# 01power.net
KiCad netlist of a schematic drawn in Altium Designer
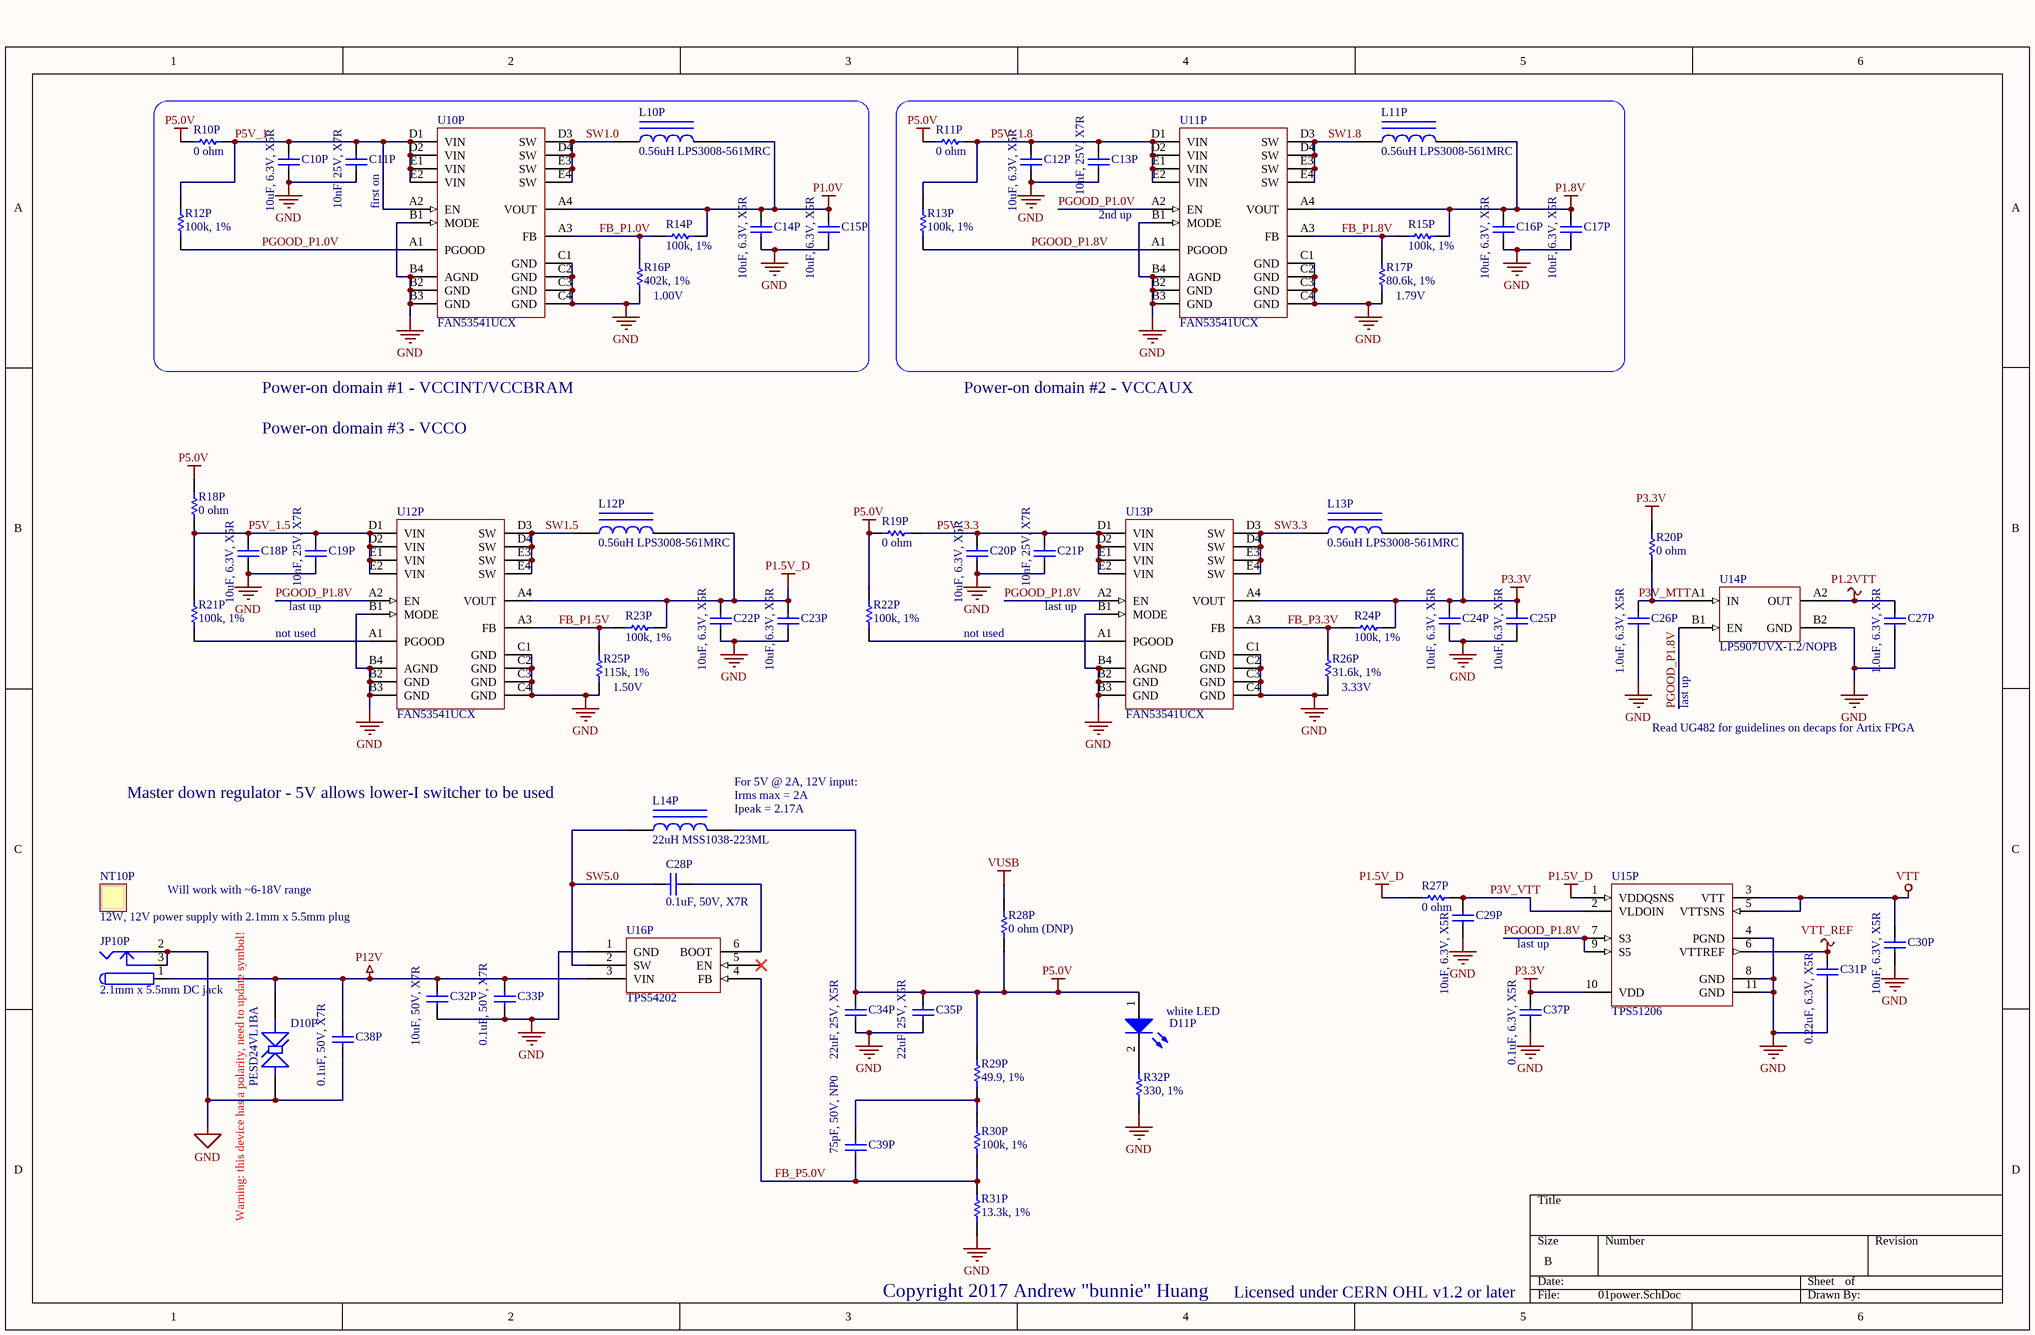
[diagram p0: 01power.SchDoc]

(export (version "E")
  (design (tool "Eeschema 10.0.6"))
  (components
    (comp (ref "C10P")
      (value "10uF, 6.3V, X5R")
      (footprint "CAPC1608N")
      (description "Capacitor (Semiconductor SIM Model)")
      (fields (field (name "MPN") "CL10A106MQ8NNNC"))
      (libsource (lib "Miscellaneous Devices") (part "Cap Semi"))
    )
    (comp (ref "C11P")
      (value "10nF, 25V, X7R")
      (footprint "CAPC1005N")
      (description "Capacitor (Semiconductor SIM Model)")
      (fields (field (name "MPN") "CL05B103KA5NNNC"))
      (libsource (lib "Miscellaneous Devices") (part "Cap Semi"))
    )
    (comp (ref "C12P")
      (value "10uF, 6.3V, X5R")
      (footprint "CAPC1608N")
      (description "Capacitor (Semiconductor SIM Model)")
      (fields (field (name "MPN") "CL10A106MQ8NNNC"))
      (libsource (lib "Miscellaneous Devices") (part "Cap Semi"))
    )
    (comp (ref "C13P")
      (value "10nF, 25V, X7R")
      (footprint "CAPC1005N")
      (description "Capacitor (Semiconductor SIM Model)")
      (fields (field (name "MPN") "CL05B103KA5NNNC"))
      (libsource (lib "Miscellaneous Devices") (part "Cap Semi"))
    )
    (comp (ref "C14P")
      (value "10uF, 6.3V, X5R")
      (footprint "CAPC1608N")
      (description "Capacitor (Semiconductor SIM Model)")
      (fields (field (name "MPN") "CL10A106MQ8NNNC"))
      (libsource (lib "Miscellaneous Devices") (part "Cap Semi"))
    )
    (comp (ref "C15P")
      (value "10uF, 6.3V, X5R")
      (footprint "CAPC1608N")
      (description "Capacitor (Semiconductor SIM Model)")
      (fields (field (name "MPN") "CL10A106MQ8NNNC"))
      (libsource (lib "Miscellaneous Devices") (part "Cap Semi"))
    )
    (comp (ref "C16P")
      (value "10uF, 6.3V, X5R")
      (footprint "CAPC1608N")
      (description "Capacitor (Semiconductor SIM Model)")
      (fields (field (name "MPN") "CL10A106MQ8NNNC"))
      (libsource (lib "Miscellaneous Devices") (part "Cap Semi"))
    )
    (comp (ref "C17P")
      (value "10uF, 6.3V, X5R")
      (footprint "CAPC1608N")
      (description "Capacitor (Semiconductor SIM Model)")
      (fields (field (name "MPN") "CL10A106MQ8NNNC"))
      (libsource (lib "Miscellaneous Devices") (part "Cap Semi"))
    )
    (comp (ref "C18P")
      (value "10uF, 6.3V, X5R")
      (footprint "CAPC1608N")
      (description "Capacitor (Semiconductor SIM Model)")
      (fields (field (name "MPN") "CL10A106MQ8NNNC"))
      (libsource (lib "Miscellaneous Devices") (part "Cap Semi"))
    )
    (comp (ref "C19P")
      (value "10nF, 25V, X7R")
      (footprint "CAPC1005N")
      (description "Capacitor (Semiconductor SIM Model)")
      (fields (field (name "MPN") "CL05B103KA5NNNC"))
      (libsource (lib "Miscellaneous Devices") (part "Cap Semi"))
    )
    (comp (ref "C20P")
      (value "10uF, 6.3V, X5R")
      (footprint "CAPC1608N")
      (description "Capacitor (Semiconductor SIM Model)")
      (fields (field (name "MPN") "CL10A106MQ8NNNC"))
      (libsource (lib "Miscellaneous Devices") (part "Cap Semi"))
    )
    (comp (ref "C21P")
      (value "10nF, 25V, X7R")
      (footprint "CAPC1005N")
      (description "Capacitor (Semiconductor SIM Model)")
      (fields (field (name "MPN") "CL05B103KA5NNNC"))
      (libsource (lib "Miscellaneous Devices") (part "Cap Semi"))
    )
    (comp (ref "C22P")
      (value "10uF, 6.3V, X5R")
      (footprint "CAPC1608N")
      (description "Capacitor (Semiconductor SIM Model)")
      (fields (field (name "MPN") "CL10A106MQ8NNNC"))
      (libsource (lib "Miscellaneous Devices") (part "Cap Semi"))
    )
    (comp (ref "C23P")
      (value "10uF, 6.3V, X5R")
      (footprint "CAPC1608N")
      (description "Capacitor (Semiconductor SIM Model)")
      (fields (field (name "MPN") "CL10A106MQ8NNNC"))
      (libsource (lib "Miscellaneous Devices") (part "Cap Semi"))
    )
    (comp (ref "C24P")
      (value "10uF, 6.3V, X5R")
      (footprint "CAPC1608N")
      (description "Capacitor (Semiconductor SIM Model)")
      (fields (field (name "MPN") "CL10A106MQ8NNNC"))
      (libsource (lib "Miscellaneous Devices") (part "Cap Semi"))
    )
    (comp (ref "C25P")
      (value "10uF, 6.3V, X5R")
      (footprint "CAPC1608N")
      (description "Capacitor (Semiconductor SIM Model)")
      (fields (field (name "MPN") "CL10A106MQ8NNNC"))
      (libsource (lib "Miscellaneous Devices") (part "Cap Semi"))
    )
    (comp (ref "C26P")
      (value "1.0uF, 6.3V, X5R")
      (footprint "CAPC0603X03L")
      (description "Capacitor (Semiconductor SIM Model)")
      (fields (field (name "MPN") "CL03A105KQ3CSNC"))
      (libsource (lib "Miscellaneous Devices") (part "Cap Semi"))
    )
    (comp (ref "C27P")
      (value "1.0uF, 6.3V, X5R")
      (footprint "CAPC0603X03L")
      (description "Capacitor (Semiconductor SIM Model)")
      (fields (field (name "MPN") "CL03A105KQ3CSNC"))
      (libsource (lib "Miscellaneous Devices") (part "Cap Semi"))
    )
    (comp (ref "C28P")
      (value "0.1uF, 50V, X7R")
      (footprint "CAPC2012N")
      (description "Capacitor (Semiconductor SIM Model)")
      (fields (field (name "MPN") "CL21B104KBCNNWC"))
      (libsource (lib "Miscellaneous Devices") (part "Cap Semi"))
    )
    (comp (ref "C29P")
      (value "10uF, 6.3V, X5R")
      (footprint "CAPC1608N")
      (description "Capacitor (Semiconductor SIM Model)")
      (fields (field (name "MPN") "CL10A106MQ8NNNC"))
      (libsource (lib "Miscellaneous Devices") (part "Cap Semi"))
    )
    (comp (ref "C30P")
      (value "10uF, 6.3V, X5R")
      (footprint "CAPC1608N")
      (description "Capacitor (Semiconductor SIM Model)")
      (fields (field (name "MPN") "CL10A106MQ8NNNC"))
      (libsource (lib "Miscellaneous Devices") (part "Cap Semi"))
    )
    (comp (ref "C31P")
      (value "0.22uF, 6.3V, X5R")
      (footprint "CAPC0603X03L")
      (description "Capacitor (Semiconductor SIM Model)")
      (fields (field (name "MPN") "CL03A224MQ3NNNC"))
      (libsource (lib "Miscellaneous Devices") (part "Cap Semi"))
    )
    (comp (ref "C32P")
      (value "10uF, 50V, X7R")
      (footprint "CAPC3216N")
      (description "Capacitor (Semiconductor SIM Model)")
      (fields (field (name "MPN") "CL31A106KBHNNNE"))
      (libsource (lib "Miscellaneous Devices") (part "Cap Semi"))
    )
    (comp (ref "C33P")
      (value "0.1uF, 50V, X7R")
      (footprint "CAPC2012N")
      (description "Capacitor (Semiconductor SIM Model)")
      (fields (field (name "MPN") "CL21B104KBCNNWC"))
      (libsource (lib "Miscellaneous Devices") (part "Cap Semi"))
    )
    (comp (ref "C34P")
      (value "22uF, 25V, X5R")
      (footprint "CAPC3216N")
      (description "Capacitor (Semiconductor SIM Model)")
      (fields (field (name "MPN") "CL31A226KAHNNNE"))
      (libsource (lib "Miscellaneous Devices") (part "Cap Semi"))
    )
    (comp (ref "C35P")
      (value "22uF, 25V, X5R")
      (footprint "CAPC3216N")
      (description "Capacitor (Semiconductor SIM Model)")
      (fields (field (name "MPN") "CL31A226KAHNNNE"))
      (libsource (lib "Miscellaneous Devices") (part "Cap Semi"))
    )
    (comp (ref "C37P")
      (value "0.1uF, 6.3V, X5R")
      (footprint "CAPC0603X03L")
      (description "Capacitor (Semiconductor SIM Model)")
      (fields (field (name "MPN") "CL03A104KQ3NNNC"))
      (libsource (lib "Miscellaneous Devices") (part "Cap Semi"))
    )
    (comp (ref "C38P")
      (value "0.1uF, 50V, X7R")
      (footprint "CAPC2012N")
      (description "Capacitor (Semiconductor SIM Model)")
      (fields (field (name "MPN") "CL21B104KBCNNWC"))
      (libsource (lib "Miscellaneous Devices") (part "Cap Semi"))
    )
    (comp (ref "C39P")
      (value "75pF, 50V, NP0")
      (footprint "CAPC1005N")
      (description "Capacitor (Semiconductor SIM Model)")
      (fields (field (name "MPN") "CL05C750JB5NNNC"))
      (libsource (lib "Miscellaneous Devices") (part "Cap Semi"))
    )
    (comp (ref "D10P")
      (value "PESD24VL1BA")
      (footprint "SOD-323")
      (description "Bidirectional zener diode, Vz 17.1V nom")
      (fields (field (name "MPN") "PESD24VL1BA,115"))
      (libsource (lib "commonsch") (part "BIDIR_ESD"))
    )
    (comp (ref "D11P")
      (value "white LED")
      (footprint "CD2012-0805")
      (description "Typical RED, GREEN, YELLOW, AMBER GaAs LED")
      (fields (field (name "MPN") "CB-2012QWC-P8"))
      (libsource (lib "Miscellaneous Devices") (part "LED2"))
    )
    (comp (ref "JP10P")
      (value "2.1mm x 5.5mm DC jack")
      (footprint "CUI_PJ_002AH_SMT")
      (description "Low Voltage Power Supply Connector")
      (fields (field (name "MPN") "PJ-002AH-SMT-TR") (field (name "PUBLISHER") "Altium Limited"))
      (libsource (lib "Miscellaneous Connectors") (part "PWR2.5"))
    )
    (comp (ref "L10P")
      (value "0.56uH LPS3008-561MRC")
      (footprint "COILCRAFT_LPS3008")
      (description "Magnetic-Core Inductor")
      (fields (field (name "MPN") "LPS3008-561MRC"))
      (libsource (lib "Miscellaneous Devices") (part "Inductor Iron"))
    )
    (comp (ref "L11P")
      (value "0.56uH LPS3008-561MRC")
      (footprint "COILCRAFT_LPS3008")
      (description "Magnetic-Core Inductor")
      (fields (field (name "MPN") "LPS3008-561MRC"))
      (libsource (lib "Miscellaneous Devices") (part "Inductor Iron"))
    )
    (comp (ref "L12P")
      (value "0.56uH LPS3008-561MRC")
      (footprint "COILCRAFT_LPS3008")
      (description "Magnetic-Core Inductor")
      (fields (field (name "MPN") "LPS3008-561MRC"))
      (libsource (lib "Miscellaneous Devices") (part "Inductor Iron"))
    )
    (comp (ref "L13P")
      (value "0.56uH LPS3008-561MRC")
      (footprint "COILCRAFT_LPS3008")
      (description "Magnetic-Core Inductor")
      (fields (field (name "MPN") "LPS3008-561MRC"))
      (libsource (lib "Miscellaneous Devices") (part "Inductor Iron"))
    )
    (comp (ref "L14P")
      (value "22uH MSS1038-223ML")
      (footprint "COILCRAFT_MSS1038")
      (description "Magnetic-Core Inductor")
      (fields (field (name "MPN") "MSS1038-223MLB"))
      (libsource (lib "Miscellaneous Devices") (part "Inductor Iron"))
    )
    (comp (ref "NT10P")
      (value "12W, 12V power supply with 2.1mm x 5.5mm plug")
      (description "Placeholder for non-board BOM items")
      (fields (field (name "MPN") "ANY"))
      (libsource (lib "commonsch") (part "NOTE"))
    )
    (comp (ref "R10P")
      (value "0 ohm")
      (footprint "RESC1608N")
      (description "Resistor")
      (fields (field (name "MPN") "ANY"))
      (libsource (lib "Miscellaneous Devices") (part "Res1"))
    )
    (comp (ref "R11P")
      (value "0 ohm")
      (footprint "RESC1608N")
      (description "Resistor")
      (fields (field (name "MPN") "ANY"))
      (libsource (lib "Miscellaneous Devices") (part "Res1"))
    )
    (comp (ref "R12P")
      (value "100k, 1%")
      (footprint "RESC1005N")
      (description "Resistor")
      (fields (field (name "MPN") "ANY"))
      (libsource (lib "Miscellaneous Devices") (part "Res1"))
    )
    (comp (ref "R13P")
      (value "100k, 1%")
      (footprint "RESC1005N")
      (description "Resistor")
      (fields (field (name "MPN") "ANY"))
      (libsource (lib "Miscellaneous Devices") (part "Res1"))
    )
    (comp (ref "R14P")
      (value "100k, 1%")
      (footprint "RESC1005N")
      (description "Resistor")
      (fields (field (name "MPN") "ANY"))
      (libsource (lib "Miscellaneous Devices") (part "Res1"))
    )
    (comp (ref "R15P")
      (value "100k, 1%")
      (footprint "RESC1005N")
      (description "Resistor")
      (fields (field (name "MPN") "ANY"))
      (libsource (lib "Miscellaneous Devices") (part "Res1"))
    )
    (comp (ref "R16P")
      (value "402k, 1%")
      (footprint "RESC1005N")
      (description "Resistor")
      (fields (field (name "MPN") "ANY"))
      (libsource (lib "Miscellaneous Devices") (part "Res1"))
    )
    (comp (ref "R17P")
      (value "80.6k, 1%")
      (footprint "RESC1005N")
      (description "Resistor")
      (fields (field (name "MPN") "ANY"))
      (libsource (lib "Miscellaneous Devices") (part "Res1"))
    )
    (comp (ref "R18P")
      (value "0 ohm")
      (footprint "RESC1608N")
      (description "Resistor")
      (fields (field (name "MPN") "ANY"))
      (libsource (lib "Miscellaneous Devices") (part "Res1"))
    )
    (comp (ref "R19P")
      (value "0 ohm")
      (footprint "RESC1608N")
      (description "Resistor")
      (fields (field (name "MPN") "ANY"))
      (libsource (lib "Miscellaneous Devices") (part "Res1"))
    )
    (comp (ref "R20P")
      (value "0 ohm")
      (footprint "RESC1608N")
      (description "Resistor")
      (fields (field (name "MPN") "ANY"))
      (libsource (lib "Miscellaneous Devices") (part "Res1"))
    )
    (comp (ref "R21P")
      (value "100k, 1%")
      (footprint "RESC1005N")
      (description "Resistor")
      (fields (field (name "MPN") "ANY"))
      (libsource (lib "Miscellaneous Devices") (part "Res1"))
    )
    (comp (ref "R22P")
      (value "100k, 1%")
      (footprint "RESC1005N")
      (description "Resistor")
      (fields (field (name "MPN") "ANY"))
      (libsource (lib "Miscellaneous Devices") (part "Res1"))
    )
    (comp (ref "R23P")
      (value "100k, 1%")
      (footprint "RESC1005N")
      (description "Resistor")
      (fields (field (name "MPN") "ANY"))
      (libsource (lib "Miscellaneous Devices") (part "Res1"))
    )
    (comp (ref "R24P")
      (value "100k, 1%")
      (footprint "RESC1005N")
      (description "Resistor")
      (fields (field (name "MPN") "ANY"))
      (libsource (lib "Miscellaneous Devices") (part "Res1"))
    )
    (comp (ref "R25P")
      (value "115k, 1%")
      (footprint "RESC1005N")
      (description "Resistor")
      (fields (field (name "MPN") "ANY"))
      (libsource (lib "Miscellaneous Devices") (part "Res1"))
    )
    (comp (ref "R26P")
      (value "31.6k, 1%")
      (footprint "RESC1005N")
      (description "Resistor")
      (fields (field (name "MPN") "ANY"))
      (libsource (lib "Miscellaneous Devices") (part "Res1"))
    )
    (comp (ref "R27P")
      (value "0 ohm")
      (footprint "RESC1608N")
      (description "Resistor")
      (fields (field (name "MPN") "ANY"))
      (libsource (lib "Miscellaneous Devices") (part "Res1"))
    )
    (comp (ref "R28P")
      (value "0 ohm (DNP)")
      (footprint "RESC1608N")
      (description "Resistor")
      (fields (field (name "MPN") "DNP"))
      (libsource (lib "Miscellaneous Devices") (part "Res1"))
    )
    (comp (ref "R29P")
      (value "49.9, 1%")
      (footprint "RESC1005N")
      (description "Resistor")
      (fields (field (name "MPN") "ANY"))
      (libsource (lib "Miscellaneous Devices") (part "Res1"))
    )
    (comp (ref "R30P")
      (value "100k, 1%")
      (footprint "RESC1005N")
      (description "Resistor")
      (fields (field (name "MPN") "ANY"))
      (libsource (lib "Miscellaneous Devices") (part "Res1"))
    )
    (comp (ref "R31P")
      (value "13.3k, 1%")
      (footprint "RESC1005N")
      (description "Resistor")
      (fields (field (name "MPN") "ANY"))
      (libsource (lib "Miscellaneous Devices") (part "Res1"))
    )
    (comp (ref "R32P")
      (value "330, 1%")
      (footprint "RESC1005N")
      (description "Resistor")
      (fields (field (name "MPN") "RS02U331FT"))
      (libsource (lib "Miscellaneous Devices") (part "Res1"))
    )
    (comp (ref "U10P")
      (value "FAN53541UCX")
      (footprint "BGA20C40P4X5_156X196X62")
      (description "2.4MHz, 5A TinyBuck Synchronous Buck Regulator")
      (libsource (lib "commonsch-new") (part "FAN53541UCX"))
    )
    (comp (ref "U11P")
      (value "FAN53541UCX")
      (footprint "BGA20C40P4X5_156X196X62")
      (description "2.4MHz, 5A TinyBuck Synchronous Buck Regulator")
      (libsource (lib "commonsch-new") (part "FAN53541UCX"))
    )
    (comp (ref "U12P")
      (value "FAN53541UCX")
      (footprint "BGA20C40P4X5_156X196X62")
      (description "2.4MHz, 5A TinyBuck Synchronous Buck Regulator")
      (libsource (lib "commonsch-new") (part "FAN53541UCX"))
    )
    (comp (ref "U13P")
      (value "FAN53541UCX")
      (footprint "BGA20C40P4X5_156X196X62")
      (description "2.4MHz, 5A TinyBuck Synchronous Buck Regulator")
      (libsource (lib "commonsch-new") (part "FAN53541UCX"))
    )
    (comp (ref "U14P")
      (value "LP5907UVX-1.2/NOPB")
      (footprint "TI_YKE004")
      (description "Ultra low-noise 250mA LDO for RF and analog in DSBGA")
      (libsource (lib "commonsch-new") (part "LP5907UVX"))
    )
    (comp (ref "U15P")
      (value "TPS51206")
      (footprint "TI-DSQ-R-PWSON-N10")
      (description "2A-peak sink/source DDR termination regulator")
      (fields (field (name "MPN") "TPS51206DSQ(T/R)"))
      (libsource (lib "temp-to-merge") (part "TPS51206"))
    )
    (comp (ref "U16P")
      (value "TPS54202")
      (footprint "SOT26A-6N")
      (description "4.5 to 28V input, 2A output, step down sync buck")
      (fields (field (name "MPN") "TPS54202DDCT"))
      (libsource (lib "commonsch-new") (part "TPS54202"))
    )
  )
  (nets
    (net (code "1") (name "/FB_P1.0V") (class "Default")
      (node (ref "R14P") (pin "1") (pinfunction "1_1") (pintype "passive"))
      (node (ref "R16P") (pin "1") (pinfunction "1_1") (pintype "passive"))
      (node (ref "U10P") (pin "A3") (pinfunction "FB_A3") (pintype "passive"))
    )
    (net (code "2") (name "/FB_P1.5V") (class "Default")
      (node (ref "R23P") (pin "1") (pinfunction "1_1") (pintype "passive"))
      (node (ref "R25P") (pin "1") (pinfunction "1_1") (pintype "passive"))
      (node (ref "U12P") (pin "A3") (pinfunction "FB_A3") (pintype "passive"))
    )
    (net (code "3") (name "/FB_P1.8V") (class "Default")
      (node (ref "R15P") (pin "1") (pinfunction "1_1") (pintype "passive"))
      (node (ref "R17P") (pin "1") (pinfunction "1_1") (pintype "passive"))
      (node (ref "U11P") (pin "A3") (pinfunction "FB_A3") (pintype "passive"))
    )
    (net (code "4") (name "/FB_P3.3V") (class "Default")
      (node (ref "R24P") (pin "1") (pinfunction "1_1") (pintype "passive"))
      (node (ref "R26P") (pin "1") (pinfunction "1_1") (pintype "passive"))
      (node (ref "U13P") (pin "A3") (pinfunction "FB_A3") (pintype "passive"))
    )
    (net (code "5") (name "/FB_P5.0V") (class "Default")
      (node (ref "C39P") (pin "2") (pinfunction "2_2") (pintype "passive"))
      (node (ref "R30P") (pin "1") (pinfunction "1_1") (pintype "passive"))
      (node (ref "R31P") (pin "2") (pinfunction "2_2") (pintype "passive"))
      (node (ref "U16P") (pin "4") (pinfunction "FB_4") (pintype "input"))
    )
    (net (code "6") (name "/P3V_MTT") (class "Default")
      (node (ref "C26P") (pin "1") (pinfunction "1_1") (pintype "passive"))
      (node (ref "R20P") (pin "1") (pinfunction "1_1") (pintype "passive"))
      (node (ref "U14P") (pin "A1") (pinfunction "IN_A1") (pintype "input"))
    )
    (net (code "7") (name "/P3V_VTT") (class "Default")
      (node (ref "C29P") (pin "1") (pinfunction "1_1") (pintype "passive"))
      (node (ref "R27P") (pin "1") (pinfunction "1_1") (pintype "passive"))
      (node (ref "U15P") (pin "2") (pinfunction "VLDOIN_2") (pintype "power_in"))
    )
    (net (code "8") (name "/P5V_1") (class "Default")
      (node (ref "C10P") (pin "1") (pinfunction "1_1") (pintype "passive"))
      (node (ref "C11P") (pin "1") (pinfunction "1_1") (pintype "passive"))
      (node (ref "R10P") (pin "2") (pinfunction "2_2") (pintype "passive"))
      (node (ref "R12P") (pin "2") (pinfunction "2_2") (pintype "passive"))
      (node (ref "U10P") (pin "A2") (pinfunction "EN_A2") (pintype "input"))
      (node (ref "U10P") (pin "D1") (pinfunction "VIN_D1") (pintype "power_in"))
      (node (ref "U10P") (pin "D2") (pinfunction "VIN_D2") (pintype "power_in"))
      (node (ref "U10P") (pin "E1") (pinfunction "VIN_E1") (pintype "power_in"))
      (node (ref "U10P") (pin "E2") (pinfunction "VIN_E2") (pintype "power_in"))
    )
    (net (code "9") (name "/P5V_1.5") (class "Default")
      (node (ref "C18P") (pin "1") (pinfunction "1_1") (pintype "passive"))
      (node (ref "C19P") (pin "1") (pinfunction "1_1") (pintype "passive"))
      (node (ref "R18P") (pin "2") (pinfunction "2_2") (pintype "passive"))
      (node (ref "R21P") (pin "1") (pinfunction "1_1") (pintype "passive"))
      (node (ref "U12P") (pin "D1") (pinfunction "VIN_D1") (pintype "power_in"))
      (node (ref "U12P") (pin "D2") (pinfunction "VIN_D2") (pintype "power_in"))
      (node (ref "U12P") (pin "E1") (pinfunction "VIN_E1") (pintype "power_in"))
      (node (ref "U12P") (pin "E2") (pinfunction "VIN_E2") (pintype "power_in"))
    )
    (net (code "10") (name "/P5V_1.8") (class "Default")
      (node (ref "C12P") (pin "1") (pinfunction "1_1") (pintype "passive"))
      (node (ref "C13P") (pin "1") (pinfunction "1_1") (pintype "passive"))
      (node (ref "R11P") (pin "2") (pinfunction "2_2") (pintype "passive"))
      (node (ref "R13P") (pin "2") (pinfunction "2_2") (pintype "passive"))
      (node (ref "U11P") (pin "D1") (pinfunction "VIN_D1") (pintype "power_in"))
      (node (ref "U11P") (pin "D2") (pinfunction "VIN_D2") (pintype "power_in"))
      (node (ref "U11P") (pin "E1") (pinfunction "VIN_E1") (pintype "power_in"))
      (node (ref "U11P") (pin "E2") (pinfunction "VIN_E2") (pintype "power_in"))
    )
    (net (code "11") (name "/P5V_3.3") (class "Default")
      (node (ref "C20P") (pin "1") (pinfunction "1_1") (pintype "passive"))
      (node (ref "C21P") (pin "1") (pinfunction "1_1") (pintype "passive"))
      (node (ref "R19P") (pin "2") (pinfunction "2_2") (pintype "passive"))
      (node (ref "U13P") (pin "D1") (pinfunction "VIN_D1") (pintype "power_in"))
      (node (ref "U13P") (pin "D2") (pinfunction "VIN_D2") (pintype "power_in"))
      (node (ref "U13P") (pin "E1") (pinfunction "VIN_E1") (pintype "power_in"))
      (node (ref "U13P") (pin "E2") (pinfunction "VIN_E2") (pintype "power_in"))
    )
    (net (code "12") (name "/PGOOD_P1.0V") (class "Default")
      (node (ref "R12P") (pin "1") (pinfunction "1_1") (pintype "passive"))
      (node (ref "U10P") (pin "A1") (pinfunction "PGOOD_A1") (pintype "open_collector"))
      (node (ref "U11P") (pin "A2") (pinfunction "EN_A2") (pintype "input"))
    )
    (net (code "13") (name "/PGOOD_P1.8V") (class "Default")
      (node (ref "R13P") (pin "1") (pinfunction "1_1") (pintype "passive"))
      (node (ref "U11P") (pin "A1") (pinfunction "PGOOD_A1") (pintype "open_collector"))
      (node (ref "U12P") (pin "A2") (pinfunction "EN_A2") (pintype "input"))
      (node (ref "U13P") (pin "A2") (pinfunction "EN_A2") (pintype "input"))
      (node (ref "U14P") (pin "B1") (pinfunction "EN_B1") (pintype "input"))
      (node (ref "U15P") (pin "7") (pinfunction "S3_7") (pintype "input"))
      (node (ref "U15P") (pin "9") (pinfunction "S5_9") (pintype "input"))
    )
    (net (code "14") (name "/SW1.0") (class "Default")
      (node (ref "L10P") (pin "1") (pinfunction "1_1") (pintype "passive"))
      (node (ref "U10P") (pin "D3") (pinfunction "SW_D3") (pintype "power_in"))
      (node (ref "U10P") (pin "D4") (pinfunction "SW_D4") (pintype "power_in"))
      (node (ref "U10P") (pin "E3") (pinfunction "SW_E3") (pintype "power_in"))
      (node (ref "U10P") (pin "E4") (pinfunction "SW_E4") (pintype "power_in"))
    )
    (net (code "15") (name "/SW1.5") (class "Default")
      (node (ref "L12P") (pin "1") (pinfunction "1_1") (pintype "passive"))
      (node (ref "U12P") (pin "D3") (pinfunction "SW_D3") (pintype "power_in"))
      (node (ref "U12P") (pin "D4") (pinfunction "SW_D4") (pintype "power_in"))
      (node (ref "U12P") (pin "E3") (pinfunction "SW_E3") (pintype "power_in"))
      (node (ref "U12P") (pin "E4") (pinfunction "SW_E4") (pintype "power_in"))
    )
    (net (code "16") (name "/SW1.8") (class "Default")
      (node (ref "L11P") (pin "1") (pinfunction "1_1") (pintype "passive"))
      (node (ref "U11P") (pin "D3") (pinfunction "SW_D3") (pintype "power_in"))
      (node (ref "U11P") (pin "D4") (pinfunction "SW_D4") (pintype "power_in"))
      (node (ref "U11P") (pin "E3") (pinfunction "SW_E3") (pintype "power_in"))
      (node (ref "U11P") (pin "E4") (pinfunction "SW_E4") (pintype "power_in"))
    )
    (net (code "17") (name "/SW3.3") (class "Default")
      (node (ref "L13P") (pin "1") (pinfunction "1_1") (pintype "passive"))
      (node (ref "U13P") (pin "D3") (pinfunction "SW_D3") (pintype "power_in"))
      (node (ref "U13P") (pin "D4") (pinfunction "SW_D4") (pintype "power_in"))
      (node (ref "U13P") (pin "E3") (pinfunction "SW_E3") (pintype "power_in"))
      (node (ref "U13P") (pin "E4") (pinfunction "SW_E4") (pintype "power_in"))
    )
    (net (code "18") (name "/SW5.0") (class "Default")
      (node (ref "C28P") (pin "1") (pinfunction "1_1") (pintype "passive"))
      (node (ref "L14P") (pin "1") (pinfunction "1_1") (pintype "passive"))
      (node (ref "U16P") (pin "2") (pinfunction "SW_2") (pintype "passive"))
    )
    (net (code "19") (name "GND") (class "Default")
      (node (ref "C10P") (pin "2") (pinfunction "2_2") (pintype "passive"))
      (node (ref "C11P") (pin "2") (pinfunction "2_2") (pintype "passive"))
      (node (ref "C12P") (pin "2") (pinfunction "2_2") (pintype "passive"))
      (node (ref "C13P") (pin "2") (pinfunction "2_2") (pintype "passive"))
      (node (ref "C14P") (pin "2") (pinfunction "2_2") (pintype "passive"))
      (node (ref "C15P") (pin "2") (pinfunction "2_2") (pintype "passive"))
      (node (ref "C16P") (pin "2") (pinfunction "2_2") (pintype "passive"))
      (node (ref "C17P") (pin "2") (pinfunction "2_2") (pintype "passive"))
      (node (ref "C18P") (pin "2") (pinfunction "2_2") (pintype "passive"))
      (node (ref "C19P") (pin "2") (pinfunction "2_2") (pintype "passive"))
      (node (ref "C20P") (pin "2") (pinfunction "2_2") (pintype "passive"))
      (node (ref "C21P") (pin "2") (pinfunction "2_2") (pintype "passive"))
      (node (ref "C22P") (pin "2") (pinfunction "2_2") (pintype "passive"))
      (node (ref "C23P") (pin "2") (pinfunction "2_2") (pintype "passive"))
      (node (ref "C24P") (pin "2") (pinfunction "2_2") (pintype "passive"))
      (node (ref "C25P") (pin "2") (pinfunction "2_2") (pintype "passive"))
      (node (ref "C26P") (pin "2") (pinfunction "2_2") (pintype "passive"))
      (node (ref "C27P") (pin "2") (pinfunction "2_2") (pintype "passive"))
      (node (ref "C29P") (pin "2") (pinfunction "2_2") (pintype "passive"))
      (node (ref "C30P") (pin "2") (pinfunction "2_2") (pintype "passive"))
      (node (ref "C31P") (pin "2") (pinfunction "2_2") (pintype "passive"))
      (node (ref "C32P") (pin "1") (pinfunction "1_1") (pintype "passive"))
      (node (ref "C33P") (pin "2") (pinfunction "2_2") (pintype "passive"))
      (node (ref "C34P") (pin "1") (pinfunction "1_1") (pintype "passive"))
      (node (ref "C35P") (pin "1") (pinfunction "1_1") (pintype "passive"))
      (node (ref "C37P") (pin "2") (pinfunction "2_2") (pintype "passive"))
      (node (ref "C38P") (pin "2") (pinfunction "2_2") (pintype "passive"))
      (node (ref "D10P") (pin "2") (pinfunction "K_2") (pintype "passive"))
      (node (ref "JP10P") (pin "2") (pintype "power_in"))
      (node (ref "JP10P") (pin "3") (pintype "power_in"))
      (node (ref "R16P") (pin "2") (pinfunction "2_2") (pintype "passive"))
      (node (ref "R17P") (pin "2") (pinfunction "2_2") (pintype "passive"))
      (node (ref "R25P") (pin "2") (pinfunction "2_2") (pintype "passive"))
      (node (ref "R26P") (pin "2") (pinfunction "2_2") (pintype "passive"))
      (node (ref "R31P") (pin "1") (pinfunction "1_1") (pintype "passive"))
      (node (ref "R32P") (pin "1") (pinfunction "1_1") (pintype "passive"))
      (node (ref "U10P") (pin "B1") (pinfunction "MODE_B1") (pintype "input"))
      (node (ref "U10P") (pin "B2") (pinfunction "GND_B2") (pintype "power_in"))
      (node (ref "U10P") (pin "B3") (pinfunction "GND_B3") (pintype "power_in"))
      (node (ref "U10P") (pin "B4") (pinfunction "AGND_B4") (pintype "power_in"))
      (node (ref "U10P") (pin "C1") (pinfunction "GND_C1") (pintype "power_in"))
      (node (ref "U10P") (pin "C2") (pinfunction "GND_C2") (pintype "power_in"))
      (node (ref "U10P") (pin "C3") (pinfunction "GND_C3") (pintype "power_in"))
      (node (ref "U10P") (pin "C4") (pinfunction "GND_C4") (pintype "power_in"))
      (node (ref "U11P") (pin "B1") (pinfunction "MODE_B1") (pintype "input"))
      (node (ref "U11P") (pin "B2") (pinfunction "GND_B2") (pintype "power_in"))
      (node (ref "U11P") (pin "B3") (pinfunction "GND_B3") (pintype "power_in"))
      (node (ref "U11P") (pin "B4") (pinfunction "AGND_B4") (pintype "power_in"))
      (node (ref "U11P") (pin "C1") (pinfunction "GND_C1") (pintype "power_in"))
      (node (ref "U11P") (pin "C2") (pinfunction "GND_C2") (pintype "power_in"))
      (node (ref "U11P") (pin "C3") (pinfunction "GND_C3") (pintype "power_in"))
      (node (ref "U11P") (pin "C4") (pinfunction "GND_C4") (pintype "power_in"))
      (node (ref "U12P") (pin "B1") (pinfunction "MODE_B1") (pintype "input"))
      (node (ref "U12P") (pin "B2") (pinfunction "GND_B2") (pintype "power_in"))
      (node (ref "U12P") (pin "B3") (pinfunction "GND_B3") (pintype "power_in"))
      (node (ref "U12P") (pin "B4") (pinfunction "AGND_B4") (pintype "power_in"))
      (node (ref "U12P") (pin "C1") (pinfunction "GND_C1") (pintype "power_in"))
      (node (ref "U12P") (pin "C2") (pinfunction "GND_C2") (pintype "power_in"))
      (node (ref "U12P") (pin "C3") (pinfunction "GND_C3") (pintype "power_in"))
      (node (ref "U12P") (pin "C4") (pinfunction "GND_C4") (pintype "power_in"))
      (node (ref "U13P") (pin "B1") (pinfunction "MODE_B1") (pintype "input"))
      (node (ref "U13P") (pin "B2") (pinfunction "GND_B2") (pintype "power_in"))
      (node (ref "U13P") (pin "B3") (pinfunction "GND_B3") (pintype "power_in"))
      (node (ref "U13P") (pin "B4") (pinfunction "AGND_B4") (pintype "power_in"))
      (node (ref "U13P") (pin "C1") (pinfunction "GND_C1") (pintype "power_in"))
      (node (ref "U13P") (pin "C2") (pinfunction "GND_C2") (pintype "power_in"))
      (node (ref "U13P") (pin "C3") (pinfunction "GND_C3") (pintype "power_in"))
      (node (ref "U13P") (pin "C4") (pinfunction "GND_C4") (pintype "power_in"))
      (node (ref "U14P") (pin "B2") (pinfunction "GND_B2") (pintype "power_in"))
      (node (ref "U15P") (pin "11") (pinfunction "GND_11") (pintype "power_in"))
      (node (ref "U15P") (pin "4") (pinfunction "PGND_4") (pintype "power_in"))
      (node (ref "U15P") (pin "8") (pinfunction "GND_8") (pintype "power_in"))
      (node (ref "U16P") (pin "1") (pinfunction "GND_1") (pintype "power_in"))
    )
    (net (code "20") (name "Net-(C39P-Pad1)") (class "Default")
      (node (ref "C39P") (pin "1") (pinfunction "1_1") (pintype "passive"))
      (node (ref "R29P") (pin "1") (pinfunction "1_1") (pintype "passive"))
      (node (ref "R30P") (pin "2") (pinfunction "2_2") (pintype "passive"))
    )
    (net (code "21") (name "Net-(D11P-K)") (class "Default")
      (node (ref "D11P") (pin "2") (pinfunction "K_2") (pintype "passive"))
      (node (ref "R32P") (pin "2") (pinfunction "2_2") (pintype "passive"))
    )
    (net (code "22") (name "Net-(U12P-PGOOD)") (class "Default")
      (node (ref "R21P") (pin "2") (pinfunction "2_2") (pintype "passive"))
      (node (ref "U12P") (pin "A1") (pinfunction "PGOOD_A1") (pintype "open_collector"))
    )
    (net (code "23") (name "Net-(U13P-PGOOD)") (class "Default")
      (node (ref "R22P") (pin "1") (pinfunction "1_1") (pintype "passive"))
      (node (ref "U13P") (pin "A1") (pinfunction "PGOOD_A1") (pintype "open_collector"))
    )
    (net (code "24") (name "Net-(U16P-BOOT)") (class "Default")
      (node (ref "C28P") (pin "2") (pinfunction "2_2") (pintype "passive"))
      (node (ref "U16P") (pin "6") (pinfunction "BOOT_6") (pintype "passive"))
    )
    (net (code "25") (name "P1.0V") (class "Default")
      (node (ref "C14P") (pin "1") (pinfunction "1_1") (pintype "passive"))
      (node (ref "C15P") (pin "1") (pinfunction "1_1") (pintype "passive"))
      (node (ref "L10P") (pin "2") (pinfunction "2_2") (pintype "passive"))
      (node (ref "R14P") (pin "2") (pinfunction "2_2") (pintype "passive"))
      (node (ref "U10P") (pin "A4") (pinfunction "VOUT_A4") (pintype "passive"))
    )
    (net (code "26") (name "P1.2VTT") (class "Default")
      (node (ref "C27P") (pin "1") (pinfunction "1_1") (pintype "passive"))
      (node (ref "U14P") (pin "A2") (pinfunction "OUT_A2") (pintype "power_in"))
    )
    (net (code "27") (name "P1.5V_D") (class "Default")
      (node (ref "C22P") (pin "1") (pinfunction "1_1") (pintype "passive"))
      (node (ref "C23P") (pin "1") (pinfunction "1_1") (pintype "passive"))
      (node (ref "L12P") (pin "2") (pinfunction "2_2") (pintype "passive"))
      (node (ref "R23P") (pin "2") (pinfunction "2_2") (pintype "passive"))
      (node (ref "R27P") (pin "2") (pinfunction "2_2") (pintype "passive"))
      (node (ref "U12P") (pin "A4") (pinfunction "VOUT_A4") (pintype "passive"))
      (node (ref "U15P") (pin "1") (pinfunction "VDDQSNS_1") (pintype "input"))
    )
    (net (code "28") (name "P1.8V") (class "Default")
      (node (ref "C16P") (pin "1") (pinfunction "1_1") (pintype "passive"))
      (node (ref "C17P") (pin "1") (pinfunction "1_1") (pintype "passive"))
      (node (ref "L11P") (pin "2") (pinfunction "2_2") (pintype "passive"))
      (node (ref "R15P") (pin "2") (pinfunction "2_2") (pintype "passive"))
      (node (ref "U11P") (pin "A4") (pinfunction "VOUT_A4") (pintype "passive"))
    )
    (net (code "29") (name "P3.3V") (class "Default")
      (node (ref "C24P") (pin "1") (pinfunction "1_1") (pintype "passive"))
      (node (ref "C25P") (pin "1") (pinfunction "1_1") (pintype "passive"))
      (node (ref "C37P") (pin "1") (pinfunction "1_1") (pintype "passive"))
      (node (ref "L13P") (pin "2") (pinfunction "2_2") (pintype "passive"))
      (node (ref "R20P") (pin "2") (pinfunction "2_2") (pintype "passive"))
      (node (ref "R24P") (pin "2") (pinfunction "2_2") (pintype "passive"))
      (node (ref "U13P") (pin "A4") (pinfunction "VOUT_A4") (pintype "passive"))
      (node (ref "U15P") (pin "10") (pinfunction "VDD_10") (pintype "power_in"))
    )
    (net (code "30") (name "P5.0V") (class "Default")
      (node (ref "C34P") (pin "2") (pinfunction "2_2") (pintype "passive"))
      (node (ref "C35P") (pin "2") (pinfunction "2_2") (pintype "passive"))
      (node (ref "D11P") (pin "1") (pinfunction "A_1") (pintype "passive"))
      (node (ref "L14P") (pin "2") (pinfunction "2_2") (pintype "passive"))
      (node (ref "R10P") (pin "1") (pinfunction "1_1") (pintype "passive"))
      (node (ref "R11P") (pin "1") (pinfunction "1_1") (pintype "passive"))
      (node (ref "R18P") (pin "1") (pinfunction "1_1") (pintype "passive"))
      (node (ref "R19P") (pin "1") (pinfunction "1_1") (pintype "passive"))
      (node (ref "R22P") (pin "2") (pinfunction "2_2") (pintype "passive"))
      (node (ref "R28P") (pin "1") (pinfunction "1_1") (pintype "passive"))
      (node (ref "R29P") (pin "2") (pinfunction "2_2") (pintype "passive"))
    )
    (net (code "31") (name "P12V") (class "Default")
      (node (ref "C32P") (pin "2") (pinfunction "2_2") (pintype "passive"))
      (node (ref "C33P") (pin "1") (pinfunction "1_1") (pintype "passive"))
      (node (ref "C38P") (pin "1") (pinfunction "1_1") (pintype "passive"))
      (node (ref "D10P") (pin "1") (pinfunction "A_1") (pintype "passive"))
      (node (ref "JP10P") (pin "1") (pintype "power_in"))
      (node (ref "U16P") (pin "3") (pinfunction "VIN_3") (pintype "power_in"))
    )
    (net (code "32") (name "VTT") (class "Default")
      (node (ref "C30P") (pin "1") (pinfunction "1_1") (pintype "passive"))
      (node (ref "U15P") (pin "3") (pinfunction "VTT_3") (pintype "power_in"))
      (node (ref "U15P") (pin "5") (pinfunction "VTTSNS_5") (pintype "input"))
    )
    (net (code "33") (name "VTT_REF") (class "Default")
      (node (ref "C31P") (pin "1") (pinfunction "1_1") (pintype "passive"))
      (node (ref "U15P") (pin "6") (pinfunction "VTTREF_6") (pintype "output"))
    )
    (net (code "34") (name "VUSB") (class "Default")
      (node (ref "R28P") (pin "2") (pinfunction "2_2") (pintype "passive"))
    )
    (net (code "35") (name "unconnected-(U16P-EN-Pad5)") (class "Default")
      (node (ref "U16P") (pin "5") (pinfunction "EN_5") (pintype "input+no_connect"))
    )
  )
)
